# Digital_Isolation.net
KiCad netlist of a schematic drawn in Altium Designer
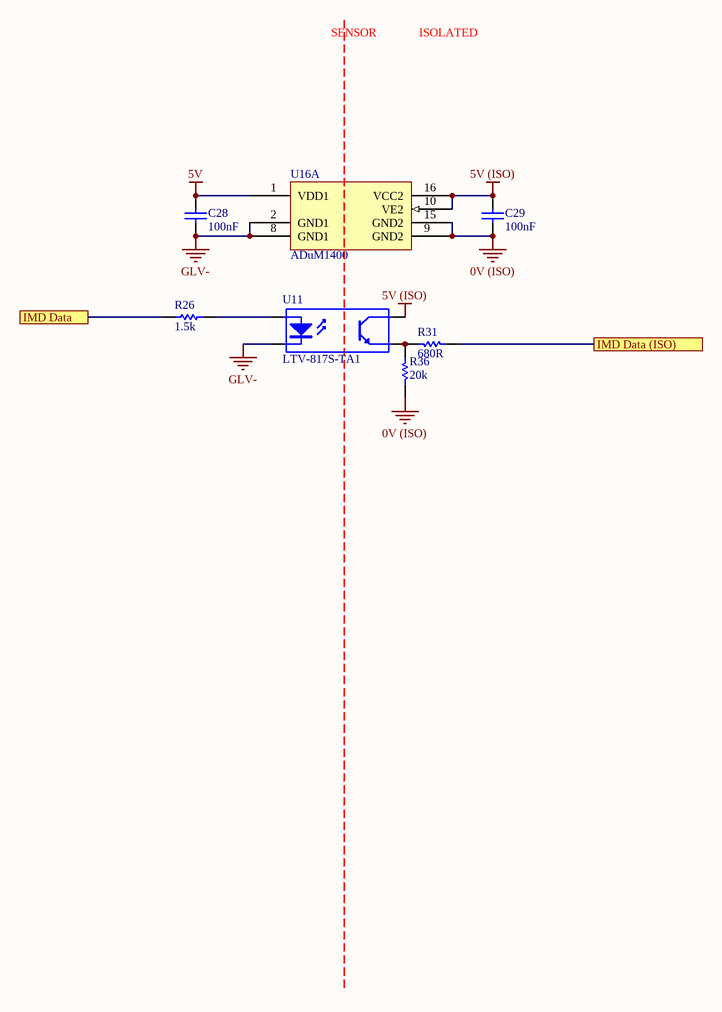
[diagram p0: Digital Isolation.SchDoc]

(export (version "E")
  (design (tool "Eeschema 10.0.6"))
  (components
    (comp (ref "C28")
      (value "100nF")
      (footprint "0805")
      (fields
        (field (name "PART NUMBER") "GCM21BR71E104KA37L")
        (field (name "TOLERANCE") "10%")
        (field (name "MANUFACTURER") "muRata")
      )
      (libsource (lib "ts_20-standard-library") (part "Capacitor"))
    )
    (comp (ref "C29")
      (value "100nF")
      (footprint "0805")
      (fields
        (field (name "PART NUMBER") "GCM21BR71E104KA37L")
        (field (name "TOLERANCE") "10%")
        (field (name "MANUFACTURER") "muRata")
      )
      (libsource (lib "ts_20-standard-library") (part "Capacitor"))
    )
    (comp (ref "R26")
      (value "1.5k")
      (footprint "0805")
      (fields
        (field (name "PART NUMBER") "RC0805FR071K5L")
        (field (name "MANUFACTURER") "YAGEO")
        (field (name "TOLERANCE") "0.01")
      )
      (libsource (lib "ts_20-standard-library") (part "Resistor"))
    )
    (comp (ref "R31")
      (value "680R")
      (footprint "0805")
      (fields
        (field (name "PART NUMBER") "RC0805FR07680RL")
        (field (name "MANUFACTURER") "YAGEO")
        (field (name "TOLERANCE") "0.01")
      )
      (libsource (lib "ts_20-standard-library") (part "Resistor"))
    )
    (comp (ref "R36")
      (value "20k")
      (footprint "0805")
      (fields
        (field (name "PART NUMBER") "RC0805FR0720KL")
        (field (name "MANUFACTURER") "YAGEO")
        (field (name "TOLERANCE") "0.01")
      )
      (libsource (lib "ts_20-standard-library") (part "Resistor"))
    )
    (comp (ref "U11")
      (value "LTV-817S-TA1")
      (footprint "ON 4-SMD")
      (description "35V 50ma Optocoupler (VF=1.2V)")
      (fields
        (field (name "MANUFACTURER") "Lite-On Inc")
        (field (name "DIGIKEY PART NUMBER") "160-1893-2-ND")
      )
      (libsource (lib "ts_20-standard-library") (part "LTV-817S-TA1"))
    )
    (comp (ref "U16")
      (value "ADuM1400")
      (footprint "AD 16-SOIC")
      (fields
        (field (name "MANUFACTURER") "Analog Devices")
        (field (name "DIGIKEY PART NUMBER") "ADUM1400WSRWZ-ND")
      )
      (libsource (lib "ts_20-standard-library") (part "ADuM1400"))
    )
  )
  (nets
    (net (code "1") (name "/IMD Data") (class "Default")
      (node (ref "R26") (pin "1") (pinfunction "1_1") (pintype "passive"))
    )
    (net (code "2") (name "/IMD Data (ISO)") (class "Default")
      (node (ref "R31") (pin "1") (pinfunction "1_1") (pintype "passive"))
    )
    (net (code "3") (name "0V (ISO)") (class "Default")
      (node (ref "C29") (pin "1") (pinfunction "1_1") (pintype "passive"))
      (node (ref "R36") (pin "1") (pinfunction "1_1") (pintype "passive"))
      (node (ref "U16") (pin "15") (pinfunction "GND2_15") (pintype "power_in"))
      (node (ref "U16") (pin "9") (pinfunction "GND2_9") (pintype "power_in"))
    )
    (net (code "4") (name "5V") (class "Default")
      (node (ref "C28") (pin "2") (pinfunction "2_2") (pintype "passive"))
      (node (ref "U16") (pin "1") (pinfunction "VDD1_1") (pintype "power_in"))
    )
    (net (code "5") (name "5V (ISO)") (class "Default")
      (node (ref "C29") (pin "2") (pinfunction "2_2") (pintype "passive"))
      (node (ref "U11") (pin "4") (pinfunction "C_4") (pintype "passive"))
      (node (ref "U16") (pin "10") (pinfunction "VE2_10") (pintype "input"))
      (node (ref "U16") (pin "16") (pinfunction "VCC2_16") (pintype "power_in"))
    )
    (net (code "6") (name "GLV-") (class "Default")
      (node (ref "C28") (pin "1") (pinfunction "1_1") (pintype "passive"))
      (node (ref "U11") (pin "2") (pinfunction "K_2") (pintype "passive"))
      (node (ref "U16") (pin "2") (pinfunction "GND1_2") (pintype "power_in"))
      (node (ref "U16") (pin "8") (pinfunction "GND1_8") (pintype "power_in"))
    )
    (net (code "7") (name "Net-(U11-A)") (class "Default")
      (node (ref "R26") (pin "2") (pinfunction "2_2") (pintype "passive"))
      (node (ref "U11") (pin "1") (pinfunction "A_1") (pintype "passive"))
    )
    (net (code "8") (name "Net-(U11-E)") (class "Default")
      (node (ref "R31") (pin "2") (pinfunction "2_2") (pintype "passive"))
      (node (ref "R36") (pin "2") (pinfunction "2_2") (pintype "passive"))
      (node (ref "U11") (pin "3") (pinfunction "E_3") (pintype "passive"))
    )
  )
)
